# uv-exposure-box-display.net
KiCad netlist of a schematic drawn in EAGLE
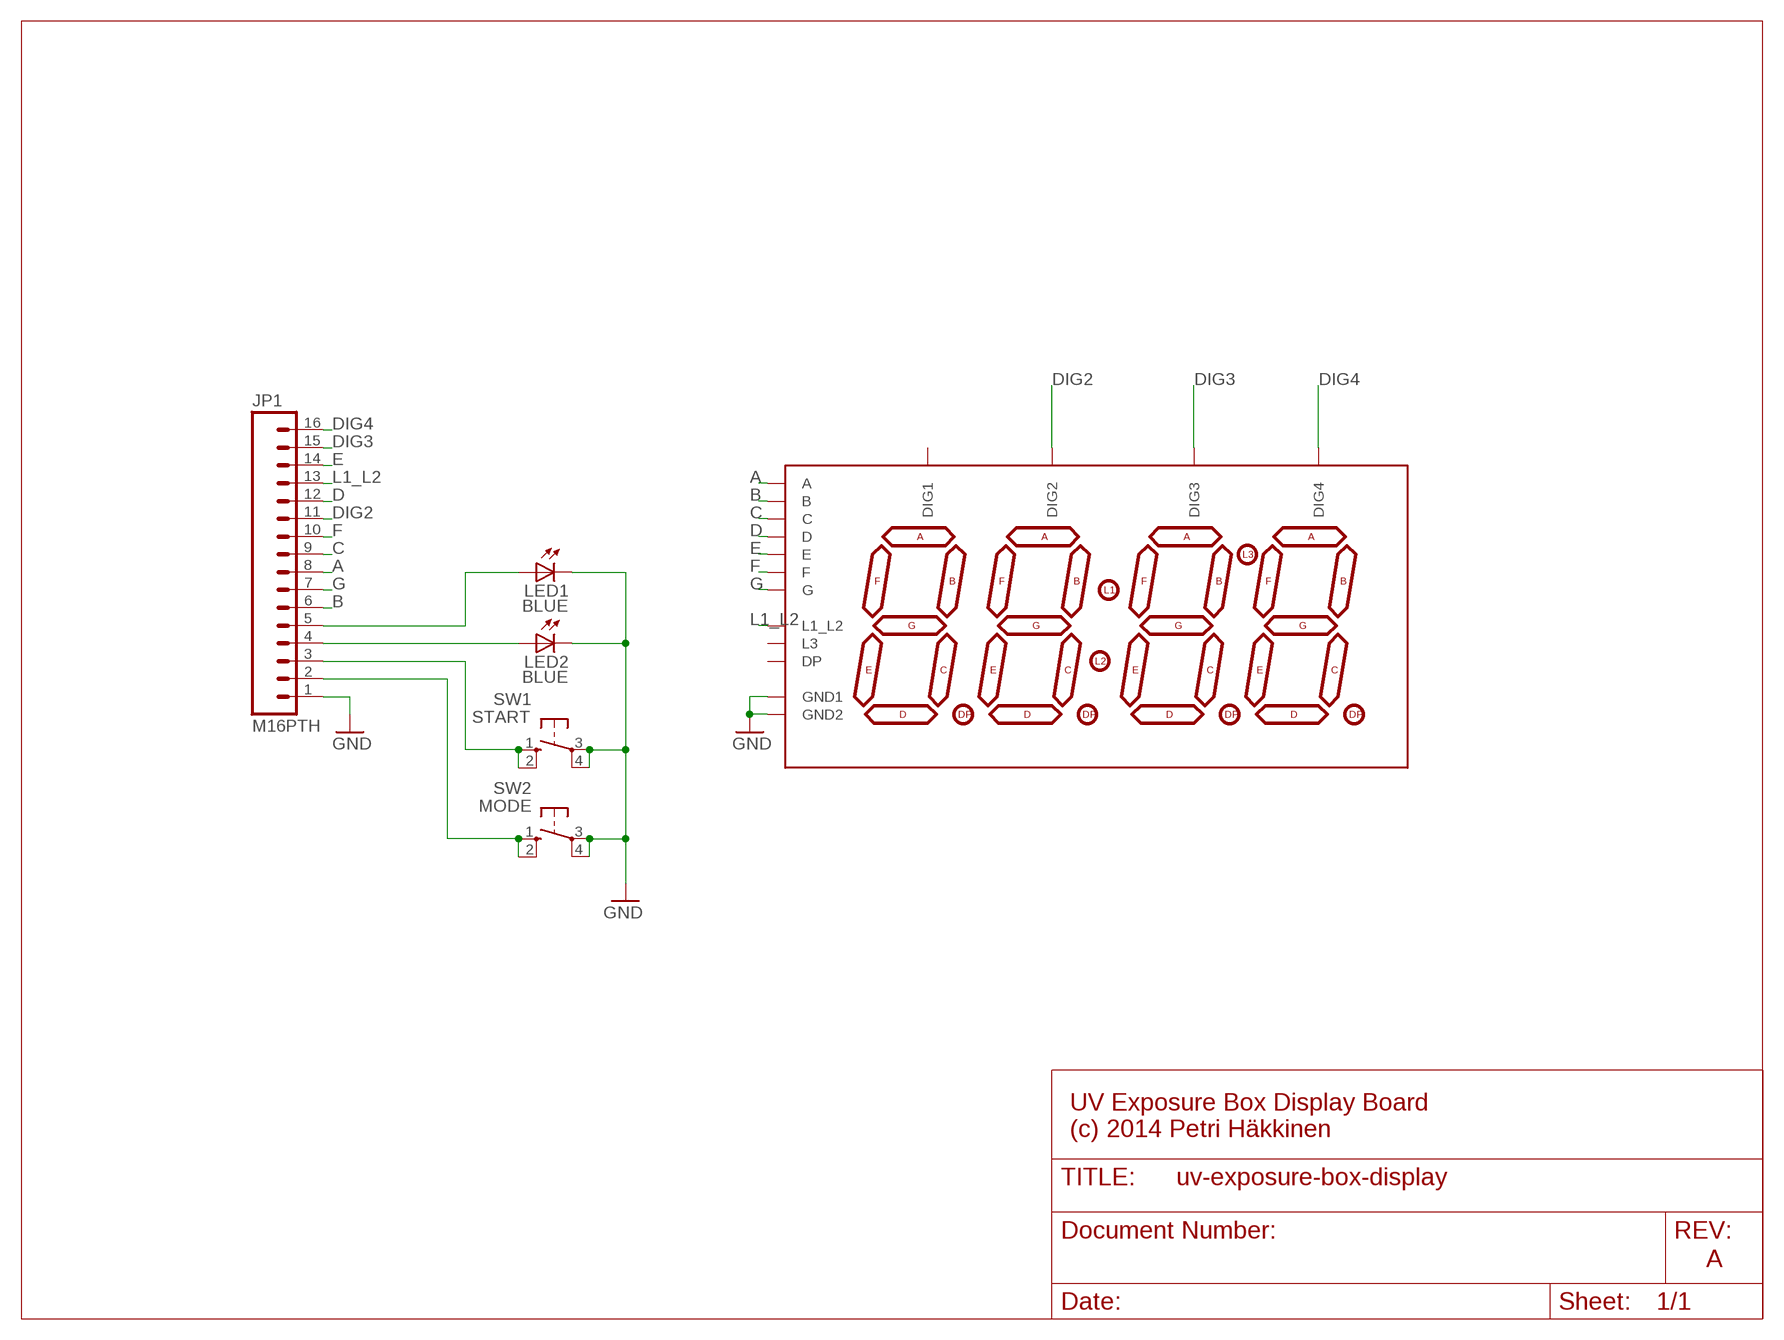
[diagram p0: schematic, sheet 1]

(export (version "E")
  (design (tool "Eeschema 10.0.6"))
  (components
    (comp (ref "JP1")
      (value "M16PTH")
      (footprint "eagle-import:1X16")
      (libsource (lib "eagle-import") (part "M16PTH"))
    )
    (comp (ref "LED1")
      (value "BLUE")
      (footprint "eagle-import:LED3MM")
      (libsource (lib "eagle-import") (part "LED3MM"))
    )
    (comp (ref "LED2")
      (value "BLUE")
      (footprint "eagle-import:LED3MM")
      (libsource (lib "eagle-import") (part "LED3MM"))
    )
    (comp (ref "SW1")
      (value "START")
      (footprint "eagle-import:B3F-10XX")
      (fields (field (name "MPN") "B3F-1000"))
      (libsource (lib "eagle-import") (part "10-XX"))
    )
    (comp (ref "SW2")
      (value "MODE")
      (footprint "eagle-import:B3F-10XX")
      (fields (field (name "MPN") "B3F-1000"))
      (libsource (lib "eagle-import") (part "10-XX"))
    )
    (comp (ref "U$1")
      (value "7-SEGMENT-4DIGIT")
      (footprint "eagle-import:7-SEGMENT-4DIGIT-YOUNGSUN")
      (libsource (lib "eagle-import") (part "7-SEGMENT-4DIGIT"))
    )
  )
  (nets
    (net (code "1") (name "/A") (class "Default")
      (node (ref "JP1") (pin "8") (pinfunction "8_8") (pintype "passive"))
      (node (ref "U$1") (pin "14") (pinfunction "A_14") (pintype "bidirectional"))
    )
    (net (code "2") (name "/B") (class "Default")
      (node (ref "JP1") (pin "6") (pinfunction "6_6") (pintype "passive"))
      (node (ref "U$1") (pin "16") (pinfunction "B_16") (pintype "bidirectional"))
    )
    (net (code "3") (name "/C") (class "Default")
      (node (ref "JP1") (pin "9") (pinfunction "9_9") (pintype "passive"))
      (node (ref "U$1") (pin "13") (pinfunction "C_13") (pintype "bidirectional"))
    )
    (net (code "4") (name "/D") (class "Default")
      (node (ref "JP1") (pin "12") (pinfunction "12_12") (pintype "passive"))
      (node (ref "U$1") (pin "3") (pinfunction "D_3") (pintype "bidirectional"))
    )
    (net (code "5") (name "/DIG2") (class "Default")
      (node (ref "JP1") (pin "11") (pinfunction "11_11") (pintype "passive"))
      (node (ref "U$1") (pin "2") (pinfunction "DIG2_2") (pintype "bidirectional"))
    )
    (net (code "6") (name "/DIG3") (class "Default")
      (node (ref "JP1") (pin "15") (pinfunction "15_15") (pintype "passive"))
      (node (ref "U$1") (pin "6") (pinfunction "DIG3_6") (pintype "bidirectional"))
    )
    (net (code "7") (name "/DIG4") (class "Default")
      (node (ref "JP1") (pin "16") (pinfunction "16_16") (pintype "passive"))
      (node (ref "U$1") (pin "8") (pinfunction "DIG4_8") (pintype "bidirectional"))
    )
    (net (code "8") (name "/E") (class "Default")
      (node (ref "JP1") (pin "14") (pinfunction "14_14") (pintype "passive"))
      (node (ref "U$1") (pin "5") (pinfunction "E_5") (pintype "bidirectional"))
    )
    (net (code "9") (name "/F") (class "Default")
      (node (ref "JP1") (pin "10") (pinfunction "10_10") (pintype "passive"))
      (node (ref "U$1") (pin "11") (pinfunction "F_11") (pintype "bidirectional"))
    )
    (net (code "10") (name "/G") (class "Default")
      (node (ref "JP1") (pin "7") (pinfunction "7_7") (pintype "passive"))
      (node (ref "U$1") (pin "15") (pinfunction "G_15") (pintype "bidirectional"))
    )
    (net (code "11") (name "/L1_L2") (class "Default")
      (node (ref "JP1") (pin "13") (pinfunction "13_13") (pintype "passive"))
      (node (ref "U$1") (pin "4") (pinfunction "L1_L2_4") (pintype "bidirectional"))
    )
    (net (code "12") (name "GND") (class "Default")
      (node (ref "JP1") (pin "1") (pinfunction "1_1") (pintype "passive"))
      (node (ref "LED1") (pin "K") (pinfunction "C_K") (pintype "passive"))
      (node (ref "LED2") (pin "K") (pinfunction "C_K") (pintype "passive"))
      (node (ref "SW1") (pin "3") (pinfunction "P_3") (pintype "passive"))
      (node (ref "SW1") (pin "4") (pinfunction "P1_4") (pintype "passive"))
      (node (ref "SW2") (pin "3") (pinfunction "P_3") (pintype "passive"))
      (node (ref "SW2") (pin "4") (pinfunction "P1_4") (pintype "passive"))
      (node (ref "U$1") (pin "12") (pinfunction "GND2_12") (pintype "bidirectional"))
      (node (ref "U$1") (pin "9") (pinfunction "GND1_9") (pintype "bidirectional"))
    )
    (net (code "13") (name "Net-(JP1-Pad4)") (class "Default")
      (node (ref "JP1") (pin "4") (pinfunction "4_4") (pintype "passive"))
      (node (ref "LED2") (pin "A") (pinfunction "A_A") (pintype "passive"))
    )
    (net (code "14") (name "Net-(JP1-Pad5)") (class "Default")
      (node (ref "JP1") (pin "5") (pinfunction "5_5") (pintype "passive"))
      (node (ref "LED1") (pin "A") (pinfunction "A_A") (pintype "passive"))
    )
    (net (code "15") (name "Net-(SW1-S)") (class "Default")
      (node (ref "JP1") (pin "3") (pinfunction "3_3") (pintype "passive"))
      (node (ref "SW1") (pin "1") (pinfunction "S_1") (pintype "passive"))
      (node (ref "SW1") (pin "2") (pinfunction "S1_2") (pintype "passive"))
    )
    (net (code "16") (name "Net-(SW2-S)") (class "Default")
      (node (ref "JP1") (pin "2") (pinfunction "2_2") (pintype "passive"))
      (node (ref "SW2") (pin "1") (pinfunction "S_1") (pintype "passive"))
      (node (ref "SW2") (pin "2") (pinfunction "S1_2") (pintype "passive"))
    )
    (net (code "17") (name "unconnected-(U$1-DIG1-Pad1)") (class "Default")
      (node (ref "U$1") (pin "1") (pinfunction "DIG1_1") (pintype "bidirectional"))
    )
    (net (code "18") (name "unconnected-(U$1-DP-Pad7)") (class "Default")
      (node (ref "U$1") (pin "7") (pinfunction "DP_7") (pintype "bidirectional"))
    )
    (net (code "19") (name "unconnected-(U$1-L3-Pad10)") (class "Default")
      (node (ref "U$1") (pin "10") (pinfunction "L3_10") (pintype "bidirectional"))
    )
  )
)
